# heating-controller.net
KiCad netlist of a schematic drawn in EAGLE
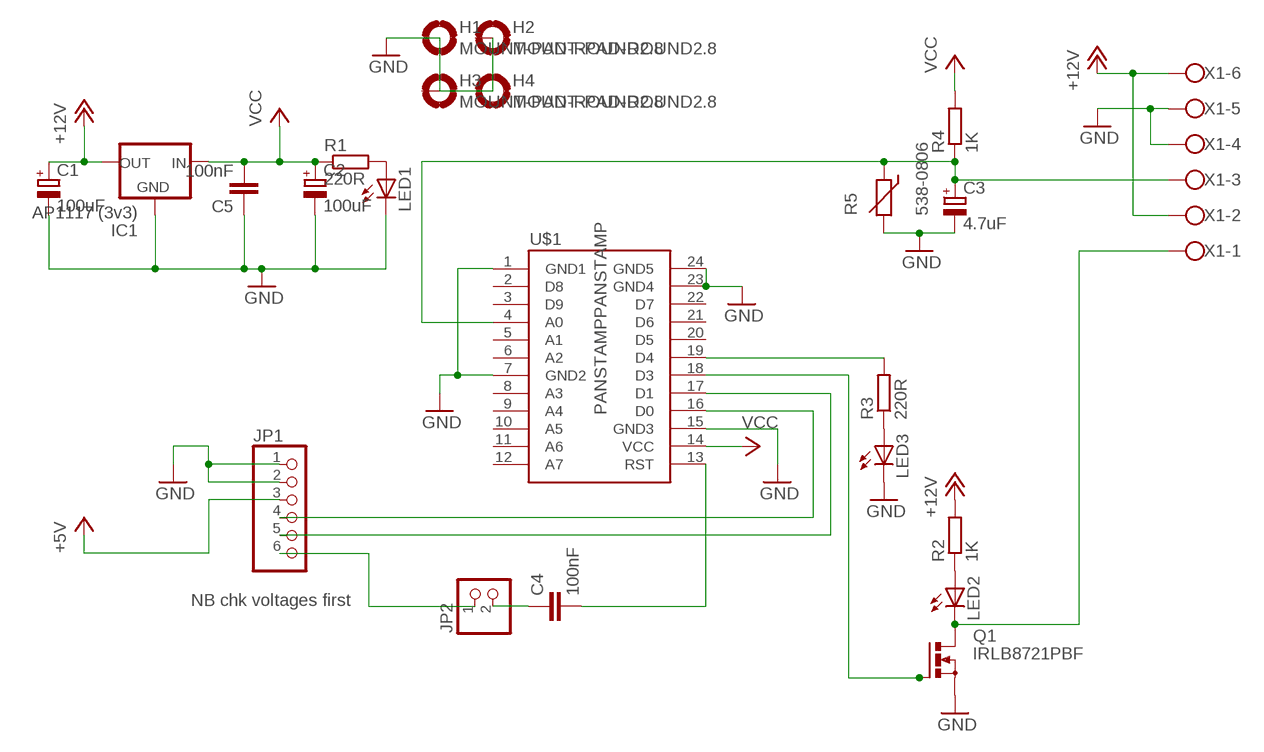
[diagram p0: schematic, sheet 1]

(export (version "E")
  (design (tool "Eeschema 10.0.6"))
  (components
    (comp (ref "C1")
      (value "100uF")
      (footprint "eagle-import:E3,5-10")
      (libsource (lib "eagle-import") (part "CPOL-EUE3.5-10"))
    )
    (comp (ref "C2")
      (value "100uF")
      (footprint "eagle-import:E3,5-10")
      (libsource (lib "eagle-import") (part "CPOL-EUE3.5-10"))
    )
    (comp (ref "C3")
      (value "4.7uF")
      (footprint "eagle-import:E3,5-10")
      (libsource (lib "eagle-import") (part "CPOL-EUE3.5-10"))
    )
    (comp (ref "C4")
      (value "100nF")
      (footprint "eagle-import:C050-024X044")
      (libsource (lib "eagle-import") (part "C-EU050-024X044"))
    )
    (comp (ref "C5")
      (value "100nF")
      (footprint "eagle-import:C050-024X044")
      (libsource (lib "eagle-import") (part "C-EU050-024X044"))
    )
    (comp (ref "H1")
      (value "MOUNT-PAD-ROUND2.8")
      (footprint "eagle-import:2,8-PAD")
      (libsource (lib "eagle-import") (part "MOUNT-PAD-ROUND2.8"))
    )
    (comp (ref "H2")
      (value "MOUNT-PAD-ROUND2.8")
      (footprint "eagle-import:2,8-PAD")
      (libsource (lib "eagle-import") (part "MOUNT-PAD-ROUND2.8"))
    )
    (comp (ref "H3")
      (value "MOUNT-PAD-ROUND2.8")
      (footprint "eagle-import:2,8-PAD")
      (libsource (lib "eagle-import") (part "MOUNT-PAD-ROUND2.8"))
    )
    (comp (ref "H4")
      (value "MOUNT-PAD-ROUND2.8")
      (footprint "eagle-import:2,8-PAD")
      (libsource (lib "eagle-import") (part "MOUNT-PAD-ROUND2.8"))
    )
    (comp (ref "IC1")
      (value "AP1117 (3v3)")
      (footprint "eagle-import:79XXS")
      (libsource (lib "eagle-import") (part "79XXS"))
    )
    (comp (ref "JP1")
      (value "PINHD-1X6")
      (footprint "eagle-import:1X06")
      (libsource (lib "eagle-import") (part "PINHD-1X6"))
    )
    (comp (ref "JP2")
      (value "PINHD-1X2")
      (footprint "eagle-import:1X02")
      (libsource (lib "eagle-import") (part "PINHD-1X2"))
    )
    (comp (ref "LED1")
      (value "LED3MM")
      (footprint "eagle-import:LED3MM")
      (libsource (lib "eagle-import") (part "LED3MM"))
    )
    (comp (ref "LED2")
      (value "LED3MM")
      (footprint "eagle-import:LED3MM")
      (libsource (lib "eagle-import") (part "LED3MM"))
    )
    (comp (ref "LED3")
      (value "LED3MM")
      (footprint "eagle-import:LED3MM")
      (libsource (lib "eagle-import") (part "LED3MM"))
    )
    (comp (ref "Q1")
      (value "IRLB8721PBF")
      (footprint "eagle-import:TO220BV")
      (libsource (lib "eagle-import") (part "PMOSFET_NTO220BV"))
    )
    (comp (ref "R1")
      (value "220R")
      (footprint "eagle-import:0207_7")
      (libsource (lib "eagle-import") (part "R-EU_0207/7"))
    )
    (comp (ref "R2")
      (value "1K")
      (footprint "eagle-import:0207_7")
      (libsource (lib "eagle-import") (part "R-EU_0207/7"))
    )
    (comp (ref "R3")
      (value "220R")
      (footprint "eagle-import:0207_7")
      (libsource (lib "eagle-import") (part "R-EU_0207/7"))
    )
    (comp (ref "R4")
      (value "1K")
      (footprint "eagle-import:0207_7")
      (libsource (lib "eagle-import") (part "R-EU_0207/7"))
    )
    (comp (ref "R5")
      (value "538-0806")
      (footprint "eagle-import:RS-2,5")
      (libsource (lib "eagle-import") (part "THERMISTOR-2,5"))
    )
    (comp (ref "U$1")
      (value "PANSTAMPPANSTAMP")
      (footprint "eagle-import:DIL24-6")
      (libsource (lib "eagle-import") (part "PANSTAMPPANSTAMP"))
    )
    (comp (ref "X1")
      (value "W237-6")
      (footprint "eagle-import:W237-6")
      (libsource (lib "eagle-import") (part "W237-6"))
    )
  )
  (nets
    (net (code "1") (name "+5V") (class "Default")
      (node (ref "JP1") (pin "3") (pinfunction "3_3") (pintype "passive"))
    )
    (net (code "2") (name "+12V") (class "Default")
      (node (ref "C1") (pin "+") (pinfunction "+_+") (pintype "passive"))
      (node (ref "IC1") (pin "OUT") (pinfunction "OUT_OUT") (pintype "passive"))
      (node (ref "R2") (pin "2") (pinfunction "2_2") (pintype "passive"))
      (node (ref "X1") (pin "2") (pinfunction "KL_2") (pintype "passive"))
      (node (ref "X1") (pin "6") (pinfunction "KL_6") (pintype "passive"))
    )
    (net (code "3") (name "GND") (class "Default")
      (node (ref "C1") (pin "-") (pinfunction "-_-") (pintype "passive"))
      (node (ref "C2") (pin "-") (pinfunction "-_-") (pintype "passive"))
      (node (ref "C3") (pin "-") (pinfunction "-_-") (pintype "passive"))
      (node (ref "C5") (pin "1") (pinfunction "1_1") (pintype "passive"))
      (node (ref "IC1") (pin "GND") (pinfunction "GND_GND") (pintype "input"))
      (node (ref "JP1") (pin "1") (pinfunction "1_1") (pintype "passive"))
      (node (ref "JP1") (pin "2") (pinfunction "2_2") (pintype "passive"))
      (node (ref "LED1") (pin "K") (pinfunction "C_K") (pintype "passive"))
      (node (ref "LED3") (pin "K") (pinfunction "C_K") (pintype "passive"))
      (node (ref "Q1") (pin "S") (pinfunction "S_S") (pintype "passive"))
      (node (ref "R5") (pin "2") (pinfunction "2_2") (pintype "passive"))
      (node (ref "U$1") (pin "1") (pinfunction "GND1_1") (pintype "power_in"))
      (node (ref "U$1") (pin "15") (pinfunction "GND3_15") (pintype "power_in"))
      (node (ref "U$1") (pin "23") (pinfunction "GND4_23") (pintype "power_in"))
      (node (ref "U$1") (pin "24") (pinfunction "GND5_24") (pintype "power_in"))
      (node (ref "U$1") (pin "7") (pinfunction "GND2_7") (pintype "power_in"))
      (node (ref "X1") (pin "4") (pinfunction "KL_4") (pintype "passive"))
      (node (ref "X1") (pin "5") (pinfunction "KL_5") (pintype "passive"))
    )
    (net (code "4") (name "Net-(C4-Pad1)") (class "Default")
      (node (ref "C4") (pin "1") (pinfunction "1_1") (pintype "passive"))
      (node (ref "JP2") (pin "2") (pinfunction "2_2") (pintype "passive"))
    )
    (net (code "5") (name "Net-(JP1-Pad6)") (class "Default")
      (node (ref "JP1") (pin "6") (pinfunction "6_6") (pintype "passive"))
      (node (ref "JP2") (pin "1") (pinfunction "1_1") (pintype "passive"))
    )
    (net (code "6") (name "Net-(LED1-PadA)") (class "Default")
      (node (ref "LED1") (pin "A") (pinfunction "A_A") (pintype "passive"))
      (node (ref "R1") (pin "2") (pinfunction "2_2") (pintype "passive"))
    )
    (net (code "7") (name "Net-(LED2-C)") (class "Default")
      (node (ref "LED2") (pin "K") (pinfunction "C_K") (pintype "passive"))
      (node (ref "Q1") (pin "D") (pinfunction "D_D") (pintype "passive"))
      (node (ref "X1") (pin "1") (pinfunction "KL_1") (pintype "passive"))
    )
    (net (code "8") (name "Net-(LED2-PadA)") (class "Default")
      (node (ref "LED2") (pin "A") (pinfunction "A_A") (pintype "passive"))
      (node (ref "R2") (pin "1") (pinfunction "1_1") (pintype "passive"))
    )
    (net (code "9") (name "Net-(LED3-PadA)") (class "Default")
      (node (ref "LED3") (pin "A") (pinfunction "A_A") (pintype "passive"))
      (node (ref "R3") (pin "1") (pinfunction "1_1") (pintype "passive"))
    )
    (net (code "10") (name "Net-(U$1-A0)") (class "Default")
      (node (ref "C3") (pin "+") (pinfunction "+_+") (pintype "passive"))
      (node (ref "R4") (pin "1") (pinfunction "1_1") (pintype "passive"))
      (node (ref "R5") (pin "1") (pinfunction "1_1") (pintype "passive"))
      (node (ref "U$1") (pin "4") (pinfunction "A0_4") (pintype "bidirectional"))
      (node (ref "X1") (pin "3") (pinfunction "KL_3") (pintype "passive"))
    )
    (net (code "11") (name "Net-(U$1-D0)") (class "Default")
      (node (ref "JP1") (pin "4") (pinfunction "4_4") (pintype "passive"))
      (node (ref "U$1") (pin "16") (pinfunction "D0_16") (pintype "bidirectional"))
    )
    (net (code "12") (name "Net-(U$1-D1)") (class "Default")
      (node (ref "JP1") (pin "5") (pinfunction "5_5") (pintype "passive"))
      (node (ref "U$1") (pin "17") (pinfunction "D1_17") (pintype "bidirectional"))
    )
    (net (code "13") (name "Net-(U$1-D3)") (class "Default")
      (node (ref "Q1") (pin "G") (pinfunction "G_G") (pintype "passive"))
      (node (ref "U$1") (pin "18") (pinfunction "D3_18") (pintype "bidirectional"))
    )
    (net (code "14") (name "Net-(U$1-D4)") (class "Default")
      (node (ref "R3") (pin "2") (pinfunction "2_2") (pintype "passive"))
      (node (ref "U$1") (pin "19") (pinfunction "D4_19") (pintype "bidirectional"))
    )
    (net (code "15") (name "Net-(U$1-RST)") (class "Default")
      (node (ref "C4") (pin "2") (pinfunction "2_2") (pintype "passive"))
      (node (ref "U$1") (pin "13") (pinfunction "RST_13") (pintype "input"))
    )
    (net (code "16") (name "VCC") (class "Default")
      (node (ref "C2") (pin "+") (pinfunction "+_+") (pintype "passive"))
      (node (ref "C5") (pin "2") (pinfunction "2_2") (pintype "passive"))
      (node (ref "IC1") (pin "IN") (pinfunction "IN_IN") (pintype "input"))
      (node (ref "R1") (pin "1") (pinfunction "1_1") (pintype "passive"))
      (node (ref "R4") (pin "2") (pinfunction "2_2") (pintype "passive"))
      (node (ref "U$1") (pin "14") (pinfunction "VCC_14") (pintype "power_in"))
    )
    (net (code "17") (name "unconnected-(H1-MOUNT-PadB2,8)") (class "Default")
      (node (ref "H1") (pin "B2,8") (pinfunction "MOUNT_B2,8") (pintype "passive"))
    )
    (net (code "18") (name "unconnected-(H2-MOUNT-PadB2,8)") (class "Default")
      (node (ref "H2") (pin "B2,8") (pinfunction "MOUNT_B2,8") (pintype "passive"))
    )
    (net (code "19") (name "unconnected-(H3-MOUNT-PadB2,8)") (class "Default")
      (node (ref "H3") (pin "B2,8") (pinfunction "MOUNT_B2,8") (pintype "passive"))
    )
    (net (code "20") (name "unconnected-(H4-MOUNT-PadB2,8)") (class "Default")
      (node (ref "H4") (pin "B2,8") (pinfunction "MOUNT_B2,8") (pintype "passive"))
    )
    (net (code "21") (name "unconnected-(U$1-A1-Pad5)") (class "Default")
      (node (ref "U$1") (pin "5") (pinfunction "A1_5") (pintype "bidirectional"))
    )
    (net (code "22") (name "unconnected-(U$1-A2-Pad6)") (class "Default")
      (node (ref "U$1") (pin "6") (pinfunction "A2_6") (pintype "bidirectional"))
    )
    (net (code "23") (name "unconnected-(U$1-A3-Pad8)") (class "Default")
      (node (ref "U$1") (pin "8") (pinfunction "A3_8") (pintype "bidirectional"))
    )
    (net (code "24") (name "unconnected-(U$1-A4-Pad9)") (class "Default")
      (node (ref "U$1") (pin "9") (pinfunction "A4_9") (pintype "bidirectional"))
    )
    (net (code "25") (name "unconnected-(U$1-A5-Pad10)") (class "Default")
      (node (ref "U$1") (pin "10") (pinfunction "A5_10") (pintype "bidirectional"))
    )
    (net (code "26") (name "unconnected-(U$1-A6-Pad11)") (class "Default")
      (node (ref "U$1") (pin "11") (pinfunction "A6_11") (pintype "bidirectional"))
    )
    (net (code "27") (name "unconnected-(U$1-A7-Pad12)") (class "Default")
      (node (ref "U$1") (pin "12") (pinfunction "A7_12") (pintype "bidirectional"))
    )
    (net (code "28") (name "unconnected-(U$1-D5-Pad20)") (class "Default")
      (node (ref "U$1") (pin "20") (pinfunction "D5_20") (pintype "bidirectional"))
    )
    (net (code "29") (name "unconnected-(U$1-D6-Pad21)") (class "Default")
      (node (ref "U$1") (pin "21") (pinfunction "D6_21") (pintype "bidirectional"))
    )
    (net (code "30") (name "unconnected-(U$1-D7-Pad22)") (class "Default")
      (node (ref "U$1") (pin "22") (pinfunction "D7_22") (pintype "bidirectional"))
    )
    (net (code "31") (name "unconnected-(U$1-D8-Pad2)") (class "Default")
      (node (ref "U$1") (pin "2") (pinfunction "D8_2") (pintype "bidirectional"))
    )
    (net (code "32") (name "unconnected-(U$1-D9-Pad3)") (class "Default")
      (node (ref "U$1") (pin "3") (pinfunction "D9_3") (pintype "bidirectional"))
    )
  )
)
